# BlueCar.net
KiCad netlist of a schematic drawn in Altium Designer
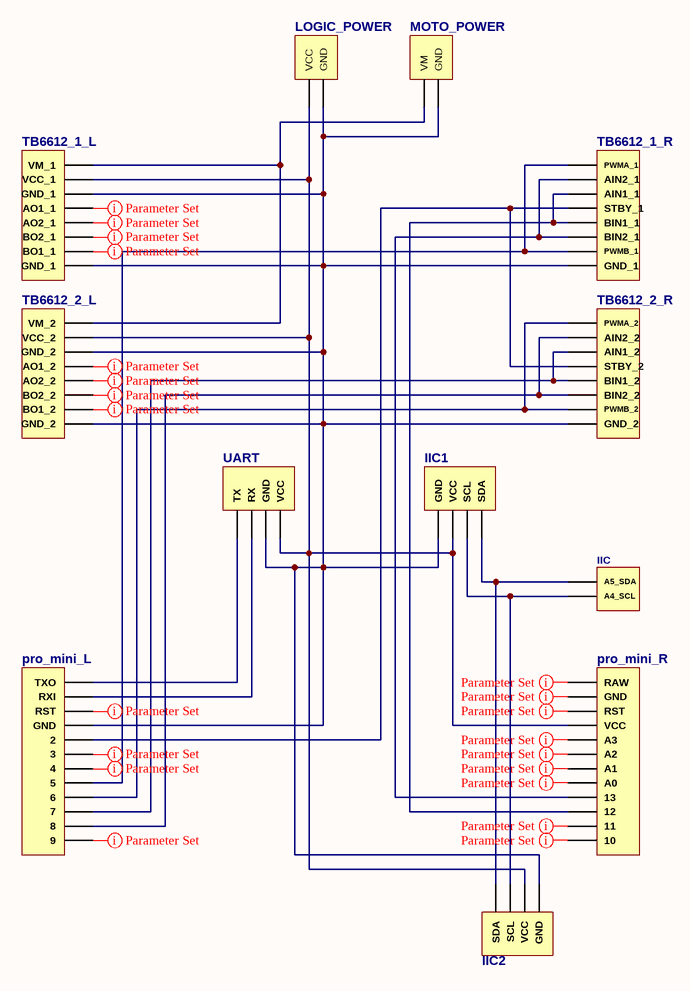
[diagram p0: BlueCar.SchDoc]

(export (version "E")
  (design (tool "Eeschema 10.0.6"))
  (components
    (comp (ref "IIC")
      (value "Header 2")
      (footprint "HDR1X2")
      (description "Header, 2-Pin")
      (fields (field (name "PUBLISHER") "Altium Limited"))
      (libsource (lib "") (part "Header 2_2"))
    )
    (comp (ref "IIC1")
      (value "Header 4")
      (footprint "HDR1X4")
      (description "Header, 4-Pin")
      (fields (field (name "PUBLISHER") "Altium Limited"))
      (libsource (lib "Miscellaneous Connectors") (part "Header 4"))
    )
    (comp (ref "IIC2")
      (value "Header 4")
      (footprint "HDR1X4")
      (description "Header, 4-Pin")
      (fields (field (name "PUBLISHER") "Altium Limited"))
      (libsource (lib "") (part "Header 4_1"))
    )
    (comp (ref "LOGIC_POWER")
      (value "Header 2")
      (footprint "HDR1X2")
      (description "Header, 2-Pin")
      (fields (field (name "PUBLISHER") "Altium Limited"))
      (libsource (lib "Miscellaneous Connectors") (part "Header 2"))
    )
    (comp (ref "MOTO_POWER")
      (value "Header 2")
      (footprint "HDR1X2")
      (description "Header, 2-Pin")
      (fields (field (name "PUBLISHER") "Altium Limited"))
      (libsource (lib "") (part "Header 2_1"))
    )
    (comp (ref "pro_mini_L")
      (value "Header 12")
      (footprint "HDR1X12")
      (description "Header, 12-Pin")
      (fields (field (name "PUBLISHER") "Altium Limited"))
      (libsource (lib "Miscellaneous Connectors") (part "Header 12"))
    )
    (comp (ref "pro_mini_R")
      (value "Header 12")
      (footprint "HDR1X12")
      (description "Header, 12-Pin")
      (fields (field (name "PUBLISHER") "Altium Limited"))
      (libsource (lib "") (part "Header 12_1"))
    )
    (comp (ref "TB6612_1_L")
      (value "Header 8")
      (footprint "HDR1X8")
      (description "Header, 8-Pin")
      (fields (field (name "PUBLISHER") "Altium Limited"))
      (libsource (lib "") (part "Header 8_3"))
    )
    (comp (ref "TB6612_1_R")
      (value "Header 8")
      (footprint "HDR1X8")
      (description "Header, 8-Pin")
      (fields (field (name "PUBLISHER") "Altium Limited"))
      (libsource (lib "") (part "Header 8_1"))
    )
    (comp (ref "TB6612_2_L")
      (value "Header 8")
      (footprint "HDR1X8")
      (description "Header, 8-Pin")
      (fields (field (name "PUBLISHER") "Altium Limited"))
      (libsource (lib "") (part "Header 8_2"))
    )
    (comp (ref "TB6612_2_R")
      (value "Header 8")
      (footprint "HDR1X8")
      (description "Header, 8-Pin")
      (fields (field (name "PUBLISHER") "Altium Limited"))
      (libsource (lib "Miscellaneous Connectors") (part "Header 8"))
    )
    (comp (ref "UART")
      (value "Header 4")
      (footprint "HDR1X4")
      (description "Header, 4-Pin")
      (fields (field (name "PUBLISHER") "Altium Limited"))
      (libsource (lib "Miscellaneous Connectors") (part "Header 4"))
    )
  )
  (nets
    (net (code "1") (name "Net-(IIC-A4_SCL)") (class "Default")
      (node (ref "IIC") (pin "2") (pinfunction "A4_SCL_2") (pintype "passive"))
      (node (ref "IIC1") (pin "3") (pinfunction "GND_3") (pintype "passive"))
      (node (ref "IIC2") (pin "3") (pinfunction "SCL_3") (pintype "passive"))
    )
    (net (code "2") (name "Net-(IIC-A5_SDA)") (class "Default")
      (node (ref "IIC") (pin "1") (pinfunction "A5_SDA_1") (pintype "passive"))
      (node (ref "IIC1") (pin "4") (pinfunction "VCC_4") (pintype "passive"))
      (node (ref "IIC2") (pin "4") (pinfunction "SDA_4") (pintype "passive"))
    )
    (net (code "3") (name "Net-(IIC1-RX)") (class "Default")
      (node (ref "IIC1") (pin "2") (pinfunction "RX_2") (pintype "passive"))
      (node (ref "IIC2") (pin "2") (pinfunction "VCC_2") (pintype "passive"))
      (node (ref "LOGIC_POWER") (pin "1") (pinfunction "VCC_1") (pintype "passive"))
      (node (ref "TB6612_1_L") (pin "2") (pinfunction "VCC_1_2") (pintype "passive"))
      (node (ref "TB6612_2_L") (pin "7") (pinfunction "VCC_2_7") (pintype "passive"))
      (node (ref "UART") (pin "4") (pinfunction "VCC_4") (pintype "passive"))
      (node (ref "pro_mini_R") (pin "4") (pinfunction "VCC_4") (pintype "passive"))
    )
    (net (code "4") (name "Net-(IIC1-TX)") (class "Default")
      (node (ref "IIC1") (pin "1") (pinfunction "TX_1") (pintype "passive"))
      (node (ref "IIC2") (pin "1") (pinfunction "GND_1") (pintype "passive"))
      (node (ref "LOGIC_POWER") (pin "2") (pinfunction "GND_2") (pintype "passive"))
      (node (ref "MOTO_POWER") (pin "2") (pinfunction "GND_2") (pintype "passive"))
      (node (ref "TB6612_1_L") (pin "3") (pinfunction "GND_1_3") (pintype "passive"))
      (node (ref "TB6612_1_L") (pin "8") (pinfunction "GND_1_8") (pintype "passive"))
      (node (ref "TB6612_1_R") (pin "8") (pinfunction "GND_1_8") (pintype "passive"))
      (node (ref "TB6612_2_L") (pin "1") (pinfunction "GND_2_1") (pintype "passive"))
      (node (ref "TB6612_2_L") (pin "6") (pinfunction "GND_2_6") (pintype "passive"))
      (node (ref "TB6612_2_R") (pin "8") (pinfunction "GND_2_8") (pintype "passive"))
      (node (ref "UART") (pin "3") (pinfunction "GND_3") (pintype "passive"))
      (node (ref "pro_mini_L") (pin "9") (pinfunction "GND_9") (pintype "passive"))
    )
    (net (code "5") (name "Net-(MOTO_POWER-VM)") (class "Default")
      (node (ref "MOTO_POWER") (pin "1") (pinfunction "VM_1") (pintype "passive"))
      (node (ref "TB6612_1_L") (pin "1") (pinfunction "VM_1_1") (pintype "passive"))
      (node (ref "TB6612_2_L") (pin "8") (pinfunction "VM_2_8") (pintype "passive"))
    )
    (net (code "6") (name "Net-(TB6612_1_R-AIN1_1)") (class "Default")
      (node (ref "TB6612_1_R") (pin "3") (pinfunction "AIN1_1_3") (pintype "passive"))
      (node (ref "TB6612_1_R") (pin "5") (pinfunction "BIN1_1_5") (pintype "passive"))
      (node (ref "pro_mini_R") (pin "10") (pinfunction "12_10") (pintype "passive"))
    )
    (net (code "7") (name "Net-(TB6612_1_R-AIN2_1)") (class "Default")
      (node (ref "TB6612_1_R") (pin "2") (pinfunction "AIN2_1_2") (pintype "passive"))
      (node (ref "TB6612_1_R") (pin "6") (pinfunction "BIN2_1_6") (pintype "passive"))
      (node (ref "pro_mini_R") (pin "9") (pinfunction "13_9") (pintype "passive"))
    )
    (net (code "8") (name "Net-(TB6612_1_R-PWMA_1)") (class "Default")
      (node (ref "TB6612_1_R") (pin "1") (pinfunction "PWMA_1_1") (pintype "passive"))
      (node (ref "TB6612_1_R") (pin "7") (pinfunction "PWMB_1_7") (pintype "passive"))
      (node (ref "pro_mini_L") (pin "5") (pinfunction "5_5") (pintype "passive"))
    )
    (net (code "9") (name "Net-(TB6612_1_R-STBY_1)") (class "Default")
      (node (ref "TB6612_1_R") (pin "4") (pinfunction "STBY_1_4") (pintype "passive"))
      (node (ref "TB6612_2_R") (pin "4") (pinfunction "STBY_2_4") (pintype "passive"))
      (node (ref "pro_mini_L") (pin "8") (pinfunction "2_8") (pintype "passive"))
    )
    (net (code "10") (name "Net-(TB6612_2_R-AIN1_2)") (class "Default")
      (node (ref "TB6612_2_R") (pin "3") (pinfunction "AIN1_2_3") (pintype "passive"))
      (node (ref "TB6612_2_R") (pin "5") (pinfunction "BIN1_2_5") (pintype "passive"))
      (node (ref "pro_mini_L") (pin "3") (pinfunction "7_3") (pintype "passive"))
    )
    (net (code "11") (name "Net-(TB6612_2_R-AIN2_2)") (class "Default")
      (node (ref "TB6612_2_R") (pin "2") (pinfunction "AIN2_2_2") (pintype "passive"))
      (node (ref "TB6612_2_R") (pin "6") (pinfunction "BIN2_2_6") (pintype "passive"))
      (node (ref "pro_mini_L") (pin "2") (pinfunction "8_2") (pintype "passive"))
    )
    (net (code "12") (name "Net-(TB6612_2_R-PWMA_2)") (class "Default")
      (node (ref "TB6612_2_R") (pin "1") (pinfunction "PWMA_2_1") (pintype "passive"))
      (node (ref "TB6612_2_R") (pin "7") (pinfunction "PWMB_2_7") (pintype "passive"))
      (node (ref "pro_mini_L") (pin "4") (pinfunction "6_4") (pintype "passive"))
    )
    (net (code "13") (name "Net-(UART-RX)") (class "Default")
      (node (ref "UART") (pin "2") (pinfunction "RX_2") (pintype "passive"))
      (node (ref "pro_mini_L") (pin "11") (pinfunction "RXI_11") (pintype "passive"))
    )
    (net (code "14") (name "Net-(UART-TX)") (class "Default")
      (node (ref "UART") (pin "1") (pinfunction "TX_1") (pintype "passive"))
      (node (ref "pro_mini_L") (pin "12") (pinfunction "TXO_12") (pintype "passive"))
    )
    (net (code "15") (name "unconnected-(TB6612_1_L-AO1_1-Pad4)") (class "Default")
      (node (ref "TB6612_1_L") (pin "4") (pinfunction "AO1_1_4") (pintype "passive"))
    )
    (net (code "16") (name "unconnected-(TB6612_1_L-AO2_1-Pad5)") (class "Default")
      (node (ref "TB6612_1_L") (pin "5") (pinfunction "AO2_1_5") (pintype "passive"))
    )
    (net (code "17") (name "unconnected-(TB6612_1_L-BO1_1-Pad7)") (class "Default")
      (node (ref "TB6612_1_L") (pin "7") (pinfunction "BO1_1_7") (pintype "passive"))
    )
    (net (code "18") (name "unconnected-(TB6612_1_L-BO2_1-Pad6)") (class "Default")
      (node (ref "TB6612_1_L") (pin "6") (pinfunction "BO2_1_6") (pintype "passive"))
    )
    (net (code "19") (name "unconnected-(TB6612_2_L-AO1_2-Pad5)") (class "Default")
      (node (ref "TB6612_2_L") (pin "5") (pinfunction "AO1_2_5") (pintype "passive"))
    )
    (net (code "20") (name "unconnected-(TB6612_2_L-AO2_2-Pad4)") (class "Default")
      (node (ref "TB6612_2_L") (pin "4") (pinfunction "AO2_2_4") (pintype "passive"))
    )
    (net (code "21") (name "unconnected-(TB6612_2_L-BO1_2-Pad2)") (class "Default")
      (node (ref "TB6612_2_L") (pin "2") (pinfunction "BO1_2_2") (pintype "passive"))
    )
    (net (code "22") (name "unconnected-(TB6612_2_L-BO2_2-Pad3)") (class "Default")
      (node (ref "TB6612_2_L") (pin "3") (pinfunction "BO2_2_3") (pintype "passive"))
    )
    (net (code "23") (name "unconnected-(pro_mini_L-3-Pad7)") (class "Default")
      (node (ref "pro_mini_L") (pin "7") (pinfunction "3_7") (pintype "passive"))
    )
    (net (code "24") (name "unconnected-(pro_mini_L-4-Pad6)") (class "Default")
      (node (ref "pro_mini_L") (pin "6") (pinfunction "4_6") (pintype "passive"))
    )
    (net (code "25") (name "unconnected-(pro_mini_L-9-Pad1)") (class "Default")
      (node (ref "pro_mini_L") (pin "1") (pinfunction "9_1") (pintype "passive"))
    )
    (net (code "26") (name "unconnected-(pro_mini_L-RST-Pad10)") (class "Default")
      (node (ref "pro_mini_L") (pin "10") (pinfunction "RST_10") (pintype "passive"))
    )
    (net (code "27") (name "unconnected-(pro_mini_R-10-Pad12)") (class "Default")
      (node (ref "pro_mini_R") (pin "12") (pinfunction "10_12") (pintype "passive"))
    )
    (net (code "28") (name "unconnected-(pro_mini_R-A0-Pad8)") (class "Default")
      (node (ref "pro_mini_R") (pin "8") (pinfunction "A0_8") (pintype "passive"))
    )
    (net (code "29") (name "unconnected-(pro_mini_R-A1-Pad7)") (class "Default")
      (node (ref "pro_mini_R") (pin "7") (pinfunction "A1_7") (pintype "passive"))
    )
    (net (code "30") (name "unconnected-(pro_mini_R-A2-Pad6)") (class "Default")
      (node (ref "pro_mini_R") (pin "6") (pinfunction "A2_6") (pintype "passive"))
    )
    (net (code "31") (name "unconnected-(pro_mini_R-A3-Pad5)") (class "Default")
      (node (ref "pro_mini_R") (pin "5") (pinfunction "A3_5") (pintype "passive"))
    )
    (net (code "32") (name "unconnected-(pro_mini_R-GND-Pad2)") (class "Default")
      (node (ref "pro_mini_R") (pin "2") (pinfunction "GND_2") (pintype "passive"))
    )
    (net (code "33") (name "unconnected-(pro_mini_R-Pad11)") (class "Default")
      (node (ref "pro_mini_R") (pin "11") (pinfunction "11_11") (pintype "passive"))
    )
    (net (code "34") (name "unconnected-(pro_mini_R-RAW-Pad1)") (class "Default")
      (node (ref "pro_mini_R") (pin "1") (pinfunction "RAW_1") (pintype "passive"))
    )
    (net (code "35") (name "unconnected-(pro_mini_R-RST-Pad3)") (class "Default")
      (node (ref "pro_mini_R") (pin "3") (pinfunction "RST_3") (pintype "passive"))
    )
  )
)
